# CLKB_uplink_phy.net
KiCad netlist of a schematic drawn in Altium Designer
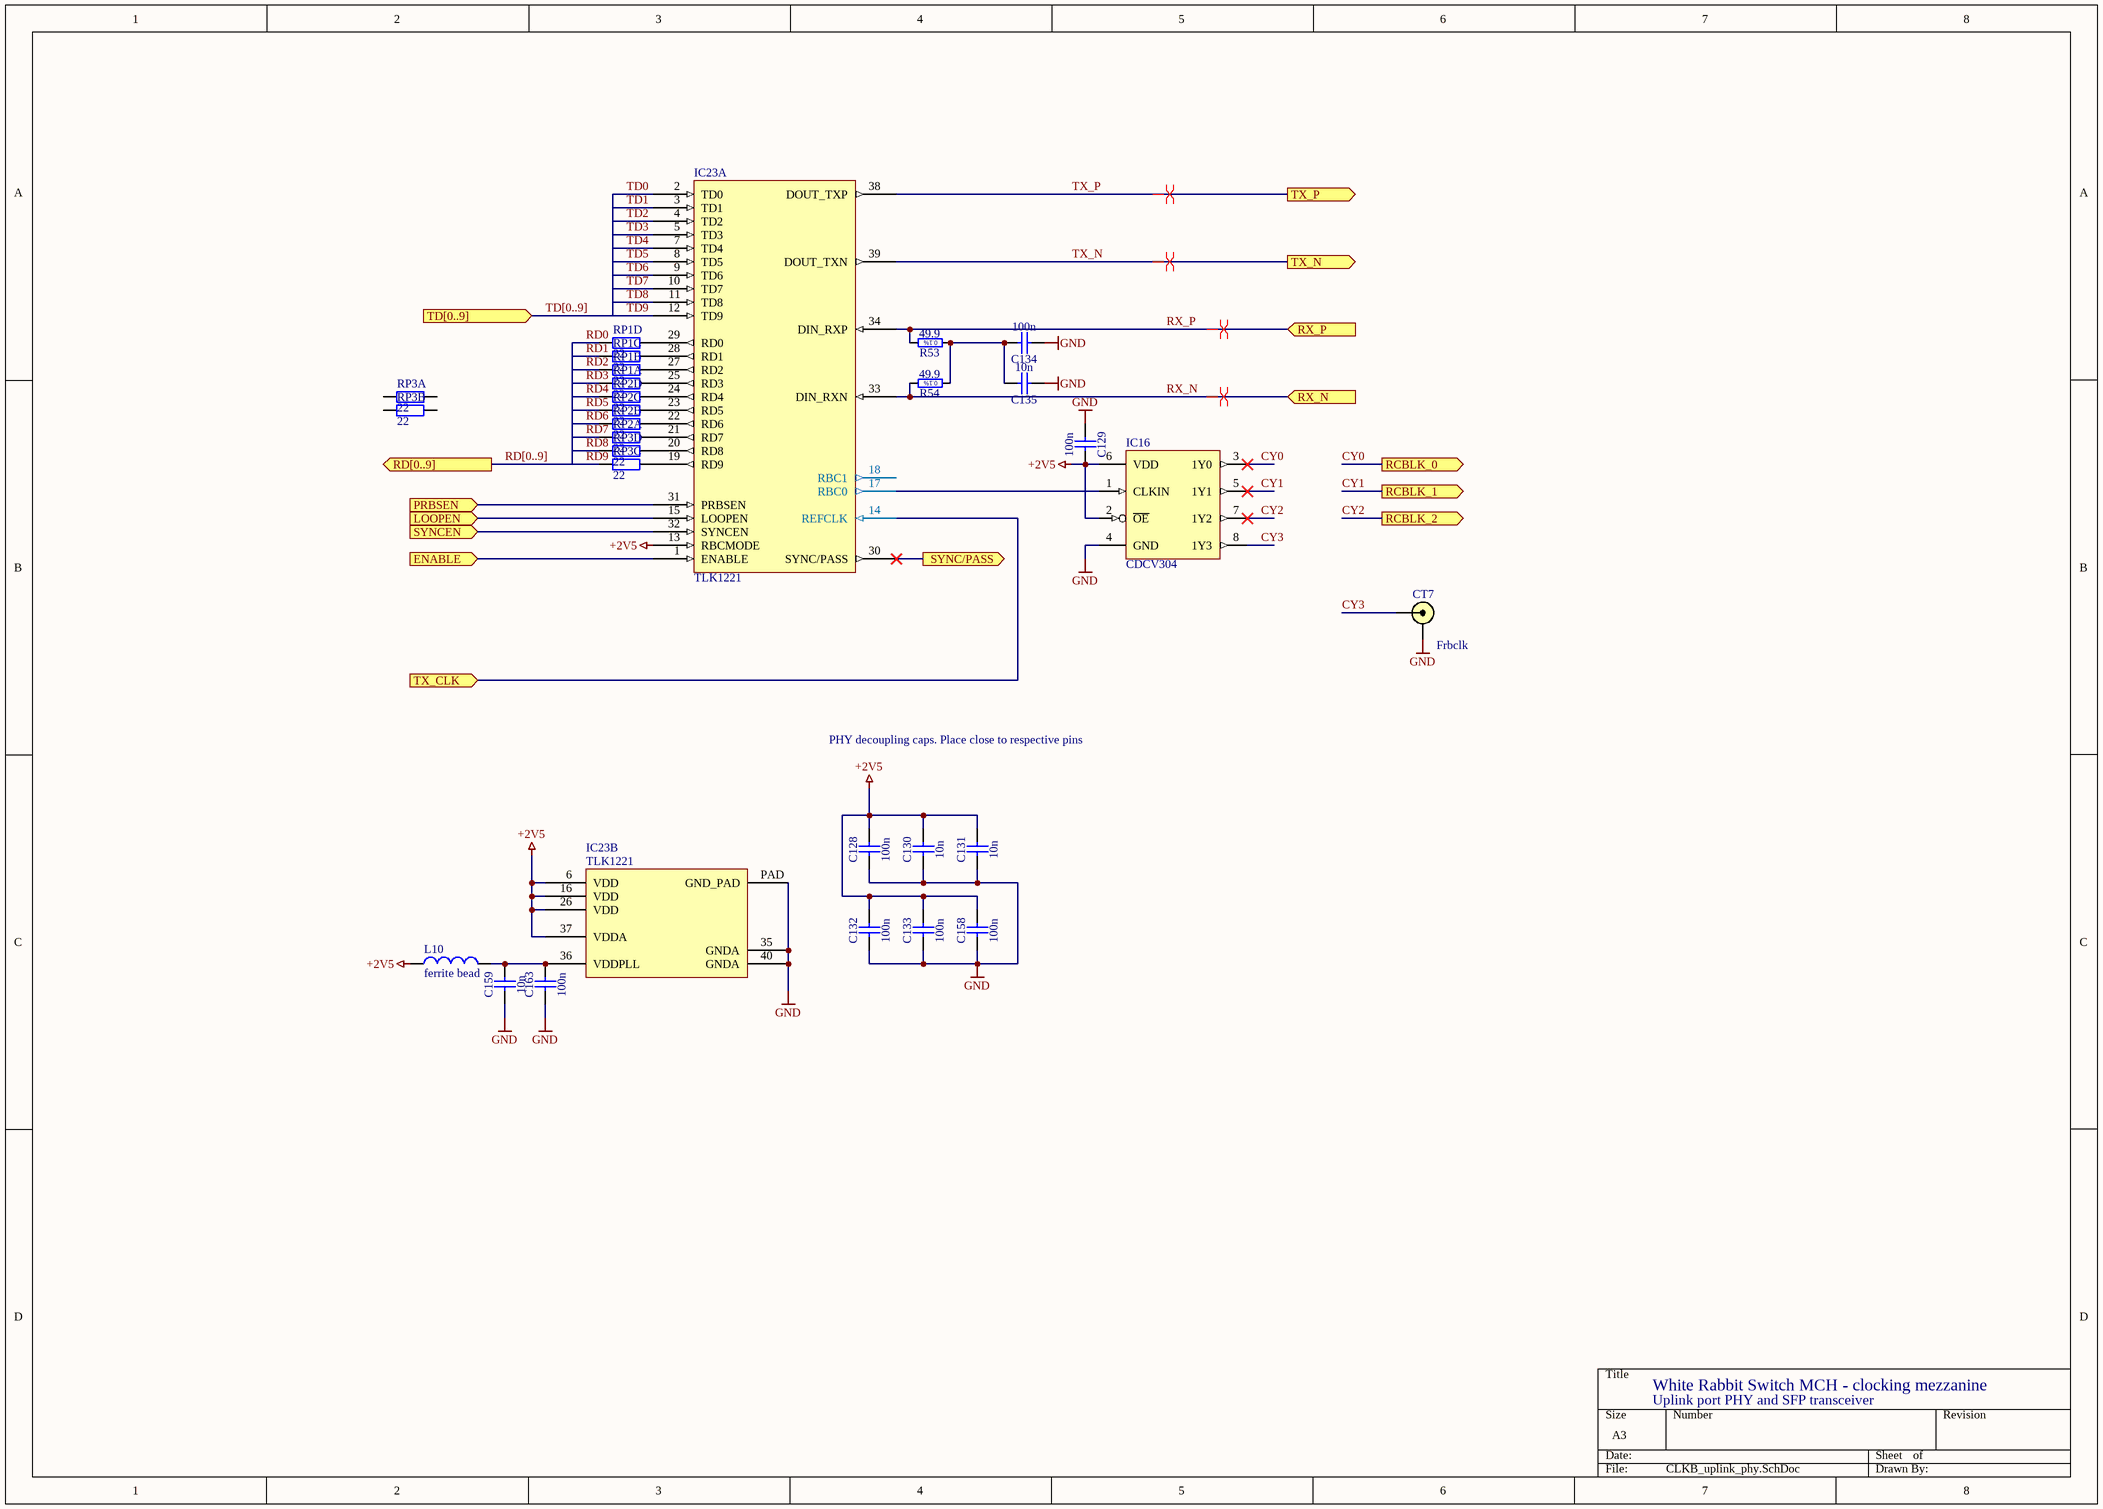
[diagram p0: CLKB_uplink_phy.SchDoc]

(export (version "E")
  (design (tool "Eeschema 10.0.6"))
  (components
    (comp (ref "C128")
      (value "100n")
      (footprint "CAPC1005X55N")
      (description "Non-polarised capacitor")
      (fields
        (field (name "PART NUMBER") "CC0402_100NF_16V_10%_X7R")
        (field (name "VOLTAGE") "16V")
        (field (name "AUTHOR") "CERN DEM JLC")
      )
      (libsource (lib "Capacitors") (part "Capacitor - non polarized"))
    )
    (comp (ref "C129")
      (value "100n")
      (footprint "CAPC1608X87N")
      (description "Non-polarised capacitor")
      (fields
        (field (name "PART NUMBER") "CC0603_100NF_50V_10%_X7R")
        (field (name "VOLTAGE") "50V")
        (field (name "AUTHOR") "CERN DEM JLC")
      )
      (libsource (lib "Capacitors") (part "Capacitor - non polarized"))
    )
    (comp (ref "C130")
      (value "10n")
      (footprint "CAPC1005X55N")
      (description "Non-polarised capacitor")
      (fields
        (field (name "PART NUMBER") "CC0402_10NF_16V_10%_X7R")
        (field (name "VOLTAGE") "16V")
        (field (name "AUTHOR") "CERN DEM JLC")
      )
      (libsource (lib "Capacitors") (part "Capacitor - non polarized"))
    )
    (comp (ref "C131")
      (value "10n")
      (footprint "CAPC1005X55N")
      (description "Non-polarised capacitor")
      (fields
        (field (name "PART NUMBER") "CC0402_10NF_16V_10%_X7R")
        (field (name "VOLTAGE") "16V")
        (field (name "AUTHOR") "CERN DEM JLC")
      )
      (libsource (lib "Capacitors") (part "Capacitor - non polarized"))
    )
    (comp (ref "C132")
      (value "100n")
      (footprint "CAPC1005X55N")
      (description "Non-polarised capacitor")
      (fields
        (field (name "PART NUMBER") "CC0402_100NF_16V_10%_X7R")
        (field (name "VOLTAGE") "16V")
        (field (name "AUTHOR") "CERN DEM JLC")
      )
      (libsource (lib "Capacitors") (part "Capacitor - non polarized"))
    )
    (comp (ref "C133")
      (value "100n")
      (footprint "CAPC1005X55N")
      (description "Non-polarised capacitor")
      (fields
        (field (name "PART NUMBER") "CC0402_100NF_16V_10%_X7R")
        (field (name "VOLTAGE") "16V")
        (field (name "AUTHOR") "CERN DEM JLC")
      )
      (libsource (lib "Capacitors") (part "Capacitor - non polarized"))
    )
    (comp (ref "C134")
      (value "100n")
      (footprint "CAPC1608X87N")
      (description "Non-polarised capacitor")
      (fields
        (field (name "PART NUMBER") "CC0603_100NF_50V_10%_X7R")
        (field (name "VOLTAGE") "50V")
        (field (name "AUTHOR") "CERN DEM JLC")
      )
      (libsource (lib "Capacitors") (part "Capacitor - non polarized"))
    )
    (comp (ref "C135")
      (value "10n")
      (footprint "CAPC1608X87N")
      (description "Non-polarised capacitor")
      (fields
        (field (name "PART NUMBER") "CC0603_10NF_50V_10%_X7R")
        (field (name "VOLTAGE") "50V")
        (field (name "AUTHOR") "CERN DEM JLC")
      )
      (libsource (lib "Capacitors") (part "Capacitor - non polarized"))
    )
    (comp (ref "C158")
      (value "100n")
      (footprint "CAPC1005X55N")
      (description "Non-polarised capacitor")
      (fields
        (field (name "PART NUMBER") "CC0402_100NF_16V_10%_X7R")
        (field (name "VOLTAGE") "16V")
        (field (name "AUTHOR") "CERN DEM JLC")
      )
      (libsource (lib "Capacitors") (part "Capacitor - non polarized"))
    )
    (comp (ref "C159")
      (value "10n")
      (footprint "CAPC1005X55N")
      (description "Non-polarised capacitor")
      (fields
        (field (name "PART NUMBER") "CC0402_10NF_16V_10%_X7R")
        (field (name "VOLTAGE") "16V")
        (field (name "AUTHOR") "CERN DEM JLC")
      )
      (libsource (lib "Capacitors") (part "Capacitor - non polarized"))
    )
    (comp (ref "C163")
      (value "100n")
      (footprint "CAPC1005X55N")
      (description "Non-polarised capacitor")
      (fields
        (field (name "PART NUMBER") "CC0402_100NF_16V_10%_X7R")
        (field (name "VOLTAGE") "16V")
        (field (name "AUTHOR") "CERN DEM JLC")
      )
      (libsource (lib "Capacitors") (part "Capacitor - non polarized"))
    )
    (comp (ref "CT7")
      (value "Frbclk")
      (footprint "CON_UFL_HIROSE_RECEPTACLE")
      (description "UFL connector testpoint")
      (libsource (lib "wr_switch") (part "CON_TESTPOINT_UFL"))
    )
    (comp (ref "IC16")
      (value "CDCV304")
      (footprint "TSOP65P490-8AN")
      (description "1:4 LVTTL fanout")
      (libsource (lib "wr_switch") (part "CDCV304"))
    )
    (comp (ref "IC23")
      (value "TLK1221")
      (footprint "QFN40_powerpad")
      (description "Texas Instruments Gigabit Ethernet PHY with deterministic clocking and LVPECL output interface")
      (libsource (lib "wr_switch") (part "TLK1221"))
    )
    (comp (ref "L10")
      (value "ferrite bead")
      (footprint "INDC1608-0603")
      (description "Ferrite bead")
      (fields (field (name "Comment") "Inductor") (field (name "PUBLISHER") "Altium Limited"))
      (libsource (lib "Miscellaneous Devices") (part "Inductor"))
    )
    (comp (ref "R53")
      (value "49.9")
      (footprint "RESC1608X55N")
      (description "Resistor - 0.1%")
      (fields
        (field (name "PART NUMBER") "R0603_49R9_0.1%_0.063W_10PPM")
        (field (name "POWER") "0.063W")
        (field (name "AUTHOR") "CERN DEM JLC")
      )
      (libsource (lib "Resistors") (part "Resistor - 0.1%"))
    )
    (comp (ref "R54")
      (value "49.9")
      (footprint "RESC1608X55N")
      (description "Resistor - 0.1%")
      (fields
        (field (name "PART NUMBER") "R0603_49R9_0.1%_0.063W_10PPM")
        (field (name "POWER") "0.063W")
        (field (name "AUTHOR") "CERN DEM JLC")
      )
      (libsource (lib "Resistors") (part "Resistor - 0.1%"))
    )
    (comp (ref "RP1")
      (value "22")
      (footprint "YC124")
      (description "4-resistor pack")
      (fields (field (name "Comment") "22 0804"))
      (libsource (lib "wr_switch") (part "Res_Pack4_22R_YC124"))
    )
    (comp (ref "RP2")
      (value "22")
      (footprint "YC124")
      (description "4-resistor pack")
      (fields (field (name "Comment") "22 0804"))
      (libsource (lib "wr_switch") (part "Res_Pack4_22R_YC124"))
    )
    (comp (ref "RP3")
      (value "22")
      (footprint "YC124")
      (description "4-resistor pack")
      (fields (field (name "Comment") "22 0804"))
      (libsource (lib "wr_switch") (part "Res_Pack4_22R_YC124"))
    )
  )
  (nets
    (net (code "1") (name "+2V5") (class "Default")
      (node (ref "C128") (pin "2") (pinfunction "2_2") (pintype "passive"))
      (node (ref "C129") (pin "2") (pinfunction "2_2") (pintype "passive"))
      (node (ref "C130") (pin "2") (pinfunction "2_2") (pintype "passive"))
      (node (ref "C131") (pin "2") (pinfunction "2_2") (pintype "passive"))
      (node (ref "C132") (pin "2") (pinfunction "2_2") (pintype "passive"))
      (node (ref "C133") (pin "2") (pinfunction "2_2") (pintype "passive"))
      (node (ref "C158") (pin "2") (pinfunction "2_2") (pintype "passive"))
      (node (ref "IC16") (pin "2") (pinfunction "~{OE}_2") (pintype "input"))
      (node (ref "IC16") (pin "6") (pinfunction "VDD_6") (pintype "power_in"))
      (node (ref "IC23") (pin "13") (pinfunction "RBCMODE_13") (pintype "input"))
      (node (ref "IC23") (pin "16") (pinfunction "VDD_16") (pintype "power_in"))
      (node (ref "IC23") (pin "26") (pinfunction "VDD_26") (pintype "power_in"))
      (node (ref "IC23") (pin "37") (pinfunction "VDDA_37") (pintype "power_in"))
      (node (ref "IC23") (pin "6") (pinfunction "VDD_6") (pintype "power_in"))
      (node (ref "L10") (pin "2") (pinfunction "2_2") (pintype "passive"))
    )
    (net (code "2") (name "/CY0") (class "Default")
      (node (ref "IC16") (pin "3") (pinfunction "1Y0_3") (pintype "output+no_connect"))
    )
    (net (code "3") (name "/CY1") (class "Default")
      (node (ref "IC16") (pin "5") (pinfunction "1Y1_5") (pintype "output+no_connect"))
    )
    (net (code "4") (name "/CY2") (class "Default")
      (node (ref "IC16") (pin "7") (pinfunction "1Y2_7") (pintype "output+no_connect"))
    )
    (net (code "5") (name "/CY3") (class "Default")
      (node (ref "CT7") (pin "1") (pintype "passive"))
      (node (ref "IC16") (pin "8") (pinfunction "1Y3_8") (pintype "output"))
    )
    (net (code "6") (name "/ENABLE") (class "Default")
      (node (ref "IC23") (pin "1") (pinfunction "ENABLE_1") (pintype "input"))
    )
    (net (code "7") (name "/LOOPEN") (class "Default")
      (node (ref "IC23") (pin "15") (pinfunction "LOOPEN_15") (pintype "input"))
    )
    (net (code "8") (name "/PRBSEN") (class "Default")
      (node (ref "IC23") (pin "31") (pinfunction "PRBSEN_31") (pintype "input"))
    )
    (net (code "9") (name "/RD0") (class "Default")
      (node (ref "RP1") (pin "4") (pinfunction "A_4") (pintype "passive"))
    )
    (net (code "10") (name "/RD1") (class "Default")
      (node (ref "RP1") (pin "3") (pinfunction "A_3") (pintype "passive"))
    )
    (net (code "11") (name "/RD2") (class "Default")
      (node (ref "RP1") (pin "2") (pinfunction "A_2") (pintype "passive"))
    )
    (net (code "12") (name "/RD3") (class "Default")
      (node (ref "RP1") (pin "1") (pinfunction "A_1") (pintype "passive"))
    )
    (net (code "13") (name "/RD4") (class "Default")
      (node (ref "RP2") (pin "4") (pinfunction "A_4") (pintype "passive"))
    )
    (net (code "14") (name "/RD5") (class "Default")
      (node (ref "RP2") (pin "3") (pinfunction "A_3") (pintype "passive"))
    )
    (net (code "15") (name "/RD6") (class "Default")
      (node (ref "RP2") (pin "2") (pinfunction "A_2") (pintype "passive"))
    )
    (net (code "16") (name "/RD7") (class "Default")
      (node (ref "RP2") (pin "1") (pinfunction "A_1") (pintype "passive"))
    )
    (net (code "17") (name "/RD8") (class "Default")
      (node (ref "RP3") (pin "4") (pinfunction "A_4") (pintype "passive"))
    )
    (net (code "18") (name "/RD9") (class "Default")
      (node (ref "RP3") (pin "3") (pinfunction "A_3") (pintype "passive"))
    )
    (net (code "20") (name "/RX_N") (class "Default")
      (node (ref "IC23") (pin "33") (pinfunction "DIN_RXN_33") (pintype "input"))
      (node (ref "R54") (pin "2") (pinfunction "2_2") (pintype "passive"))
    )
    (net (code "21") (name "/RX_P") (class "Default")
      (node (ref "IC23") (pin "34") (pinfunction "DIN_RXP_34") (pintype "input"))
      (node (ref "R53") (pin "2") (pinfunction "2_2") (pintype "passive"))
    )
    (net (code "22") (name "/SYNCEN") (class "Default")
      (node (ref "IC23") (pin "32") (pinfunction "SYNCEN_32") (pintype "input"))
    )
    (net (code "23") (name "/SYNC{slash}PASS") (class "Default")
      (node (ref "IC23") (pin "30") (pinfunction "SYNC/PASS_30") (pintype "output+no_connect"))
    )
    (net (code "24") (name "/TD0") (class "Default")
      (node (ref "IC23") (pin "2") (pinfunction "TD0_2") (pintype "input"))
    )
    (net (code "25") (name "/TD1") (class "Default")
      (node (ref "IC23") (pin "3") (pinfunction "TD1_3") (pintype "input"))
    )
    (net (code "26") (name "/TD2") (class "Default")
      (node (ref "IC23") (pin "4") (pinfunction "TD2_4") (pintype "input"))
    )
    (net (code "27") (name "/TD3") (class "Default")
      (node (ref "IC23") (pin "5") (pinfunction "TD3_5") (pintype "input"))
    )
    (net (code "28") (name "/TD4") (class "Default")
      (node (ref "IC23") (pin "7") (pinfunction "TD4_7") (pintype "input"))
    )
    (net (code "29") (name "/TD5") (class "Default")
      (node (ref "IC23") (pin "8") (pinfunction "TD5_8") (pintype "input"))
    )
    (net (code "30") (name "/TD6") (class "Default")
      (node (ref "IC23") (pin "9") (pinfunction "TD6_9") (pintype "input"))
    )
    (net (code "31") (name "/TD7") (class "Default")
      (node (ref "IC23") (pin "10") (pinfunction "TD7_10") (pintype "input"))
    )
    (net (code "32") (name "/TD8") (class "Default")
      (node (ref "IC23") (pin "11") (pinfunction "TD8_11") (pintype "input"))
    )
    (net (code "33") (name "/TD9") (class "Default")
      (node (ref "IC23") (pin "12") (pinfunction "TD9_12") (pintype "input"))
    )
    (net (code "35") (name "/TX_CLK") (class "Default")
      (node (ref "IC23") (pin "14") (pinfunction "REFCLK_14") (pintype "input"))
    )
    (net (code "36") (name "/TX_N") (class "Default")
      (node (ref "IC23") (pin "39") (pinfunction "DOUT_TXN_39") (pintype "output"))
    )
    (net (code "37") (name "/TX_P") (class "Default")
      (node (ref "IC23") (pin "38") (pinfunction "DOUT_TXP_38") (pintype "output"))
    )
    (net (code "38") (name "GND") (class "Default")
      (node (ref "C128") (pin "1") (pinfunction "1_1") (pintype "passive"))
      (node (ref "C129") (pin "1") (pinfunction "1_1") (pintype "passive"))
      (node (ref "C130") (pin "1") (pinfunction "1_1") (pintype "passive"))
      (node (ref "C131") (pin "1") (pinfunction "1_1") (pintype "passive"))
      (node (ref "C132") (pin "1") (pinfunction "1_1") (pintype "passive"))
      (node (ref "C133") (pin "1") (pinfunction "1_1") (pintype "passive"))
      (node (ref "C134") (pin "1") (pinfunction "1_1") (pintype "passive"))
      (node (ref "C135") (pin "1") (pinfunction "1_1") (pintype "passive"))
      (node (ref "C158") (pin "1") (pinfunction "1_1") (pintype "passive"))
      (node (ref "C159") (pin "1") (pinfunction "1_1") (pintype "passive"))
      (node (ref "C163") (pin "1") (pinfunction "1_1") (pintype "passive"))
      (node (ref "CT7") (pin "2") (pintype "passive"))
      (node (ref "IC16") (pin "4") (pinfunction "GND_4") (pintype "power_in"))
      (node (ref "IC23") (pin "35") (pinfunction "GNDA_35") (pintype "power_in"))
      (node (ref "IC23") (pin "40") (pinfunction "GNDA_40") (pintype "power_in"))
      (node (ref "IC23") (pin "PAD") (pinfunction "GND_PAD_PAD") (pintype "power_in"))
    )
    (net (code "39") (name "Net-(C134-Pad2)") (class "Default")
      (node (ref "C134") (pin "2") (pinfunction "2_2") (pintype "passive"))
      (node (ref "C135") (pin "2") (pinfunction "2_2") (pintype "passive"))
      (node (ref "R53") (pin "1") (pinfunction "1_1") (pintype "passive"))
      (node (ref "R54") (pin "1") (pinfunction "1_1") (pintype "passive"))
    )
    (net (code "40") (name "Net-(IC16-CLKIN)") (class "Default")
      (node (ref "IC16") (pin "1") (pinfunction "CLKIN_1") (pintype "input"))
      (node (ref "IC23") (pin "17") (pinfunction "RBC0_17") (pintype "output"))
    )
    (net (code "41") (name "Net-(IC23A-RD0)") (class "Default")
      (node (ref "IC23") (pin "29") (pinfunction "RD0_29") (pintype "output"))
      (node (ref "RP1") (pin "5") (pinfunction "B_5") (pintype "passive"))
    )
    (net (code "42") (name "Net-(IC23A-RD1)") (class "Default")
      (node (ref "IC23") (pin "28") (pinfunction "RD1_28") (pintype "output"))
      (node (ref "RP1") (pin "6") (pinfunction "B_6") (pintype "passive"))
    )
    (net (code "43") (name "Net-(IC23A-RD2)") (class "Default")
      (node (ref "IC23") (pin "27") (pinfunction "RD2_27") (pintype "output"))
      (node (ref "RP1") (pin "7") (pinfunction "B_7") (pintype "passive"))
    )
    (net (code "44") (name "Net-(IC23A-RD3)") (class "Default")
      (node (ref "IC23") (pin "25") (pinfunction "RD3_25") (pintype "output"))
      (node (ref "RP1") (pin "8") (pinfunction "B_8") (pintype "passive"))
    )
    (net (code "45") (name "Net-(IC23A-RD4)") (class "Default")
      (node (ref "IC23") (pin "24") (pinfunction "RD4_24") (pintype "output"))
      (node (ref "RP2") (pin "5") (pinfunction "B_5") (pintype "passive"))
    )
    (net (code "46") (name "Net-(IC23A-RD5)") (class "Default")
      (node (ref "IC23") (pin "23") (pinfunction "RD5_23") (pintype "output"))
      (node (ref "RP2") (pin "6") (pinfunction "B_6") (pintype "passive"))
    )
    (net (code "47") (name "Net-(IC23A-RD6)") (class "Default")
      (node (ref "IC23") (pin "22") (pinfunction "RD6_22") (pintype "output"))
      (node (ref "RP2") (pin "7") (pinfunction "B_7") (pintype "passive"))
    )
    (net (code "48") (name "Net-(IC23A-RD7)") (class "Default")
      (node (ref "IC23") (pin "21") (pinfunction "RD7_21") (pintype "output"))
      (node (ref "RP2") (pin "8") (pinfunction "B_8") (pintype "passive"))
    )
    (net (code "49") (name "Net-(IC23A-RD8)") (class "Default")
      (node (ref "IC23") (pin "20") (pinfunction "RD8_20") (pintype "output"))
      (node (ref "RP3") (pin "5") (pinfunction "B_5") (pintype "passive"))
    )
    (net (code "50") (name "Net-(IC23A-RD9)") (class "Default")
      (node (ref "IC23") (pin "19") (pinfunction "RD9_19") (pintype "output"))
      (node (ref "RP3") (pin "6") (pinfunction "B_6") (pintype "passive"))
    )
    (net (code "51") (name "Net-(IC23B-VDDPLL)") (class "Default")
      (node (ref "C159") (pin "2") (pinfunction "2_2") (pintype "passive"))
      (node (ref "C163") (pin "2") (pinfunction "2_2") (pintype "passive"))
      (node (ref "IC23") (pin "36") (pinfunction "VDDPLL_36") (pintype "power_in"))
      (node (ref "L10") (pin "1") (pinfunction "1_1") (pintype "passive"))
    )
    (net (code "52") (name "unconnected-(IC23A-RBC1-Pad18)") (class "Default")
      (node (ref "IC23") (pin "18") (pinfunction "RBC1_18") (pintype "output"))
    )
    (net (code "53") (name "unconnected-(RP3A-A-Pad1)") (class "Default")
      (node (ref "RP3") (pin "1") (pinfunction "A_1") (pintype "passive"))
    )
    (net (code "54") (name "unconnected-(RP3A-B-Pad8)") (class "Default")
      (node (ref "RP3") (pin "8") (pinfunction "B_8") (pintype "passive"))
    )
    (net (code "55") (name "unconnected-(RP3B-A-Pad2)") (class "Default")
      (node (ref "RP3") (pin "2") (pinfunction "A_2") (pintype "passive"))
    )
    (net (code "56") (name "unconnected-(RP3B-B-Pad7)") (class "Default")
      (node (ref "RP3") (pin "7") (pinfunction "B_7") (pintype "passive"))
    )
  )
)
